# design.net
KiCad netlist of a schematic drawn in EAGLE
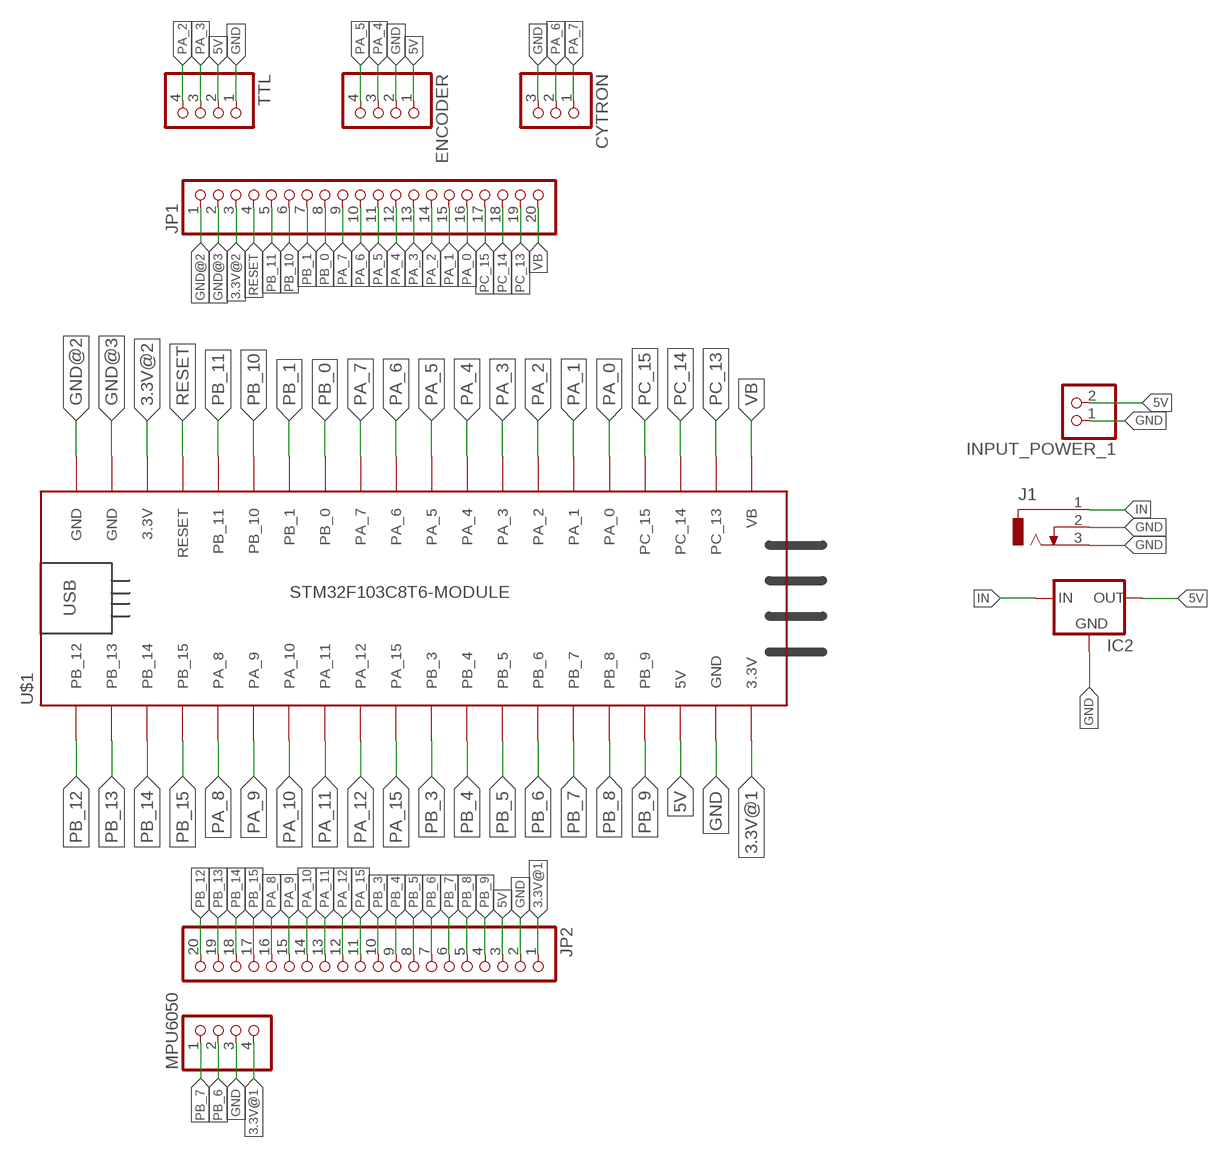
[diagram p0: schematic, sheet 1]

(export (version "E")
  (design (tool "Eeschema 10.0.6"))
  (components
    (comp (ref "CYTRON")
      (value "PINHD-1X3")
      (footprint "eagle-import:1X03")
      (libsource (lib "eagle-import") (part "PINHD-1X3"))
    )
    (comp (ref "ENCODER")
      (value "PINHD-1X4")
      (footprint "eagle-import:1X04")
      (libsource (lib "eagle-import") (part "PINHD-1X4"))
    )
    (comp (ref "IC2")
      (value "78XXS")
      (footprint "eagle-import:78XXS")
      (libsource (lib "eagle-import") (part "78XXS"))
    )
    (comp (ref "INPUT_POWER_1")
      (value "PINHD-1X2")
      (footprint "eagle-import:1X02")
      (libsource (lib "eagle-import") (part "PINHD-1X2"))
    )
    (comp (ref "J1")
      (value "CON_JACK")
      (footprint "eagle-import:DCJ0303")
      (libsource (lib "eagle-import") (part "CON_JACK"))
    )
    (comp (ref "JP1")
      (value "PINHD-1X20")
      (footprint "eagle-import:1X20")
      (libsource (lib "eagle-import") (part "PINHD-1X20"))
    )
    (comp (ref "JP2")
      (value "PINHD-1X20")
      (footprint "eagle-import:1X20")
      (libsource (lib "eagle-import") (part "PINHD-1X20"))
    )
    (comp (ref "MPU6050")
      (value "PINHD-1X4")
      (footprint "eagle-import:1X04")
      (libsource (lib "eagle-import") (part "PINHD-1X4"))
    )
    (comp (ref "TTL")
      (value "PINHD-1X4")
      (footprint "eagle-import:1X04")
      (libsource (lib "eagle-import") (part "PINHD-1X4"))
    )
    (comp (ref "U$1")
      (value "STM32F103C8T6-MODULE")
      (footprint "eagle-import:STM32F103C8T6-MODULE")
      (libsource (lib "eagle-import") (part "STM32F103C8T6-MODULE"))
    )
  )
  (nets
    (net (code "1") (name "3.3V@1") (class "Default")
      (node (ref "JP2") (pin "1") (pinfunction "1_1") (pintype "passive"))
      (node (ref "MPU6050") (pin "4") (pinfunction "4_4") (pintype "passive"))
      (node (ref "U$1") (pin "3.3V_1") (pinfunction "3.3V_3.3V_1") (pintype "bidirectional"))
    )
    (net (code "2") (name "3.3V@2") (class "Default")
      (node (ref "JP1") (pin "3") (pinfunction "3_3") (pintype "passive"))
      (node (ref "U$1") (pin "3.3V_2") (pinfunction "3.3V_3.3V_2") (pintype "bidirectional"))
    )
    (net (code "3") (name "5V") (class "Default")
      (node (ref "ENCODER") (pin "1") (pinfunction "1_1") (pintype "passive"))
      (node (ref "IC2") (pin "OUT") (pinfunction "OUT_OUT") (pintype "passive"))
      (node (ref "INPUT_POWER_1") (pin "2") (pinfunction "2_2") (pintype "passive"))
      (node (ref "JP2") (pin "3") (pinfunction "3_3") (pintype "passive"))
      (node (ref "TTL") (pin "2") (pinfunction "2_2") (pintype "passive"))
      (node (ref "U$1") (pin "5V") (pinfunction "5V_5V") (pintype "bidirectional"))
    )
    (net (code "4") (name "GND") (class "Default")
      (node (ref "CYTRON") (pin "3") (pinfunction "3_3") (pintype "passive"))
      (node (ref "ENCODER") (pin "2") (pinfunction "2_2") (pintype "passive"))
      (node (ref "IC2") (pin "GND") (pinfunction "GND_GND") (pintype "input"))
      (node (ref "INPUT_POWER_1") (pin "1") (pinfunction "1_1") (pintype "passive"))
      (node (ref "J1") (pin "2") (pinfunction "2_2") (pintype "passive"))
      (node (ref "J1") (pin "3") (pinfunction "3_3") (pintype "passive"))
      (node (ref "JP2") (pin "2") (pinfunction "2_2") (pintype "passive"))
      (node (ref "MPU6050") (pin "3") (pinfunction "3_3") (pintype "passive"))
      (node (ref "TTL") (pin "1") (pinfunction "1_1") (pintype "passive"))
      (node (ref "U$1") (pin "GND_1") (pinfunction "GND_GND_1") (pintype "bidirectional"))
    )
    (net (code "5") (name "GND@2") (class "Default")
      (node (ref "JP1") (pin "1") (pinfunction "1_1") (pintype "passive"))
      (node (ref "U$1") (pin "GND_3") (pinfunction "GND_GND_3") (pintype "power_in"))
    )
    (net (code "6") (name "GND@3") (class "Default")
      (node (ref "JP1") (pin "2") (pinfunction "2_2") (pintype "passive"))
      (node (ref "U$1") (pin "GND_2") (pinfunction "GND_GND_2") (pintype "bidirectional"))
    )
    (net (code "7") (name "IN") (class "Default")
      (node (ref "IC2") (pin "IN") (pinfunction "IN_IN") (pintype "input"))
      (node (ref "J1") (pin "1") (pinfunction "1_1") (pintype "passive"))
    )
    (net (code "8") (name "PA_0") (class "Default")
      (node (ref "JP1") (pin "16") (pinfunction "16_16") (pintype "passive"))
      (node (ref "U$1") (pin "PA_0") (pinfunction "PA_0_PA_0") (pintype "bidirectional"))
    )
    (net (code "9") (name "PA_1") (class "Default")
      (node (ref "JP1") (pin "15") (pinfunction "15_15") (pintype "passive"))
      (node (ref "U$1") (pin "PA_1") (pinfunction "PA_1_PA_1") (pintype "bidirectional"))
    )
    (net (code "10") (name "PA_2") (class "Default")
      (node (ref "JP1") (pin "14") (pinfunction "14_14") (pintype "passive"))
      (node (ref "TTL") (pin "4") (pinfunction "4_4") (pintype "passive"))
      (node (ref "U$1") (pin "PA_2") (pinfunction "PA_2_PA_2") (pintype "bidirectional"))
    )
    (net (code "11") (name "PA_3") (class "Default")
      (node (ref "JP1") (pin "13") (pinfunction "13_13") (pintype "passive"))
      (node (ref "TTL") (pin "3") (pinfunction "3_3") (pintype "passive"))
      (node (ref "U$1") (pin "PA_3") (pinfunction "PA_3_PA_3") (pintype "bidirectional"))
    )
    (net (code "12") (name "PA_4") (class "Default")
      (node (ref "ENCODER") (pin "3") (pinfunction "3_3") (pintype "passive"))
      (node (ref "JP1") (pin "12") (pinfunction "12_12") (pintype "passive"))
      (node (ref "U$1") (pin "PA_4") (pinfunction "PA_4_PA_4") (pintype "bidirectional"))
    )
    (net (code "13") (name "PA_5") (class "Default")
      (node (ref "ENCODER") (pin "4") (pinfunction "4_4") (pintype "passive"))
      (node (ref "JP1") (pin "11") (pinfunction "11_11") (pintype "passive"))
      (node (ref "U$1") (pin "PA_5") (pinfunction "PA_5_PA_5") (pintype "bidirectional"))
    )
    (net (code "14") (name "PA_6") (class "Default")
      (node (ref "CYTRON") (pin "2") (pinfunction "2_2") (pintype "passive"))
      (node (ref "JP1") (pin "10") (pinfunction "10_10") (pintype "passive"))
      (node (ref "U$1") (pin "PA_6") (pinfunction "PA_6_PA_6") (pintype "bidirectional"))
    )
    (net (code "15") (name "PA_7") (class "Default")
      (node (ref "CYTRON") (pin "1") (pinfunction "1_1") (pintype "passive"))
      (node (ref "JP1") (pin "9") (pinfunction "9_9") (pintype "passive"))
      (node (ref "U$1") (pin "PA_7") (pinfunction "PA_7_PA_7") (pintype "bidirectional"))
    )
    (net (code "16") (name "PA_8") (class "Default")
      (node (ref "JP2") (pin "16") (pinfunction "16_16") (pintype "passive"))
      (node (ref "U$1") (pin "PA_8") (pinfunction "PA_8_PA_8") (pintype "bidirectional"))
    )
    (net (code "17") (name "PA_9") (class "Default")
      (node (ref "JP2") (pin "15") (pinfunction "15_15") (pintype "passive"))
      (node (ref "U$1") (pin "PA_9") (pinfunction "PA_9_PA_9") (pintype "bidirectional"))
    )
    (net (code "18") (name "PA_10") (class "Default")
      (node (ref "JP2") (pin "14") (pinfunction "14_14") (pintype "passive"))
      (node (ref "U$1") (pin "PA_10") (pinfunction "PA_10_PA_10") (pintype "bidirectional"))
    )
    (net (code "19") (name "PA_11") (class "Default")
      (node (ref "JP2") (pin "13") (pinfunction "13_13") (pintype "passive"))
      (node (ref "U$1") (pin "PA_11") (pinfunction "PA_11_PA_11") (pintype "bidirectional"))
    )
    (net (code "20") (name "PA_12") (class "Default")
      (node (ref "JP2") (pin "12") (pinfunction "12_12") (pintype "passive"))
      (node (ref "U$1") (pin "PA_12") (pinfunction "PA_12_PA_12") (pintype "bidirectional"))
    )
    (net (code "21") (name "PA_15") (class "Default")
      (node (ref "JP2") (pin "11") (pinfunction "11_11") (pintype "passive"))
      (node (ref "U$1") (pin "PA_15") (pinfunction "PA_15_PA_15") (pintype "bidirectional"))
    )
    (net (code "22") (name "PB_0") (class "Default")
      (node (ref "JP1") (pin "8") (pinfunction "8_8") (pintype "passive"))
      (node (ref "U$1") (pin "PB_0") (pinfunction "PB_0_PB_0") (pintype "bidirectional"))
    )
    (net (code "23") (name "PB_1") (class "Default")
      (node (ref "JP1") (pin "7") (pinfunction "7_7") (pintype "passive"))
      (node (ref "U$1") (pin "PB_1") (pinfunction "PB_1_PB_1") (pintype "bidirectional"))
    )
    (net (code "24") (name "PB_3") (class "Default")
      (node (ref "JP2") (pin "10") (pinfunction "10_10") (pintype "passive"))
      (node (ref "U$1") (pin "PB_3") (pinfunction "PB_3_PB_3") (pintype "bidirectional"))
    )
    (net (code "25") (name "PB_4") (class "Default")
      (node (ref "JP2") (pin "9") (pinfunction "9_9") (pintype "passive"))
      (node (ref "U$1") (pin "PB_4") (pinfunction "PB_4_PB_4") (pintype "bidirectional"))
    )
    (net (code "26") (name "PB_5") (class "Default")
      (node (ref "JP2") (pin "8") (pinfunction "8_8") (pintype "passive"))
      (node (ref "U$1") (pin "PB_5") (pinfunction "PB_5_PB_5") (pintype "bidirectional"))
    )
    (net (code "27") (name "PB_6") (class "Default")
      (node (ref "JP2") (pin "7") (pinfunction "7_7") (pintype "passive"))
      (node (ref "MPU6050") (pin "2") (pinfunction "2_2") (pintype "passive"))
      (node (ref "U$1") (pin "PB_6") (pinfunction "PB_6_PB_6") (pintype "bidirectional"))
    )
    (net (code "28") (name "PB_7") (class "Default")
      (node (ref "JP2") (pin "6") (pinfunction "6_6") (pintype "passive"))
      (node (ref "MPU6050") (pin "1") (pinfunction "1_1") (pintype "passive"))
      (node (ref "U$1") (pin "PB_7") (pinfunction "PB_7_PB_7") (pintype "bidirectional"))
    )
    (net (code "29") (name "PB_8") (class "Default")
      (node (ref "JP2") (pin "5") (pinfunction "5_5") (pintype "passive"))
      (node (ref "U$1") (pin "PB_8") (pinfunction "PB_8_PB_8") (pintype "bidirectional"))
    )
    (net (code "30") (name "PB_9") (class "Default")
      (node (ref "JP2") (pin "4") (pinfunction "4_4") (pintype "passive"))
      (node (ref "U$1") (pin "PB_9") (pinfunction "PB_9_PB_9") (pintype "bidirectional"))
    )
    (net (code "31") (name "PB_10") (class "Default")
      (node (ref "JP1") (pin "6") (pinfunction "6_6") (pintype "passive"))
      (node (ref "U$1") (pin "PB_10") (pinfunction "PB_10_PB_10") (pintype "bidirectional"))
    )
    (net (code "32") (name "PB_11") (class "Default")
      (node (ref "JP1") (pin "5") (pinfunction "5_5") (pintype "passive"))
      (node (ref "U$1") (pin "PB_11") (pinfunction "PB_11_PB_11") (pintype "bidirectional"))
    )
    (net (code "33") (name "PB_12") (class "Default")
      (node (ref "JP2") (pin "20") (pinfunction "20_20") (pintype "passive"))
      (node (ref "U$1") (pin "PB_12") (pinfunction "PB_12_PB_12") (pintype "bidirectional"))
    )
    (net (code "34") (name "PB_13") (class "Default")
      (node (ref "JP2") (pin "19") (pinfunction "19_19") (pintype "passive"))
      (node (ref "U$1") (pin "PB_13") (pinfunction "PB_13_PB_13") (pintype "bidirectional"))
    )
    (net (code "35") (name "PB_14") (class "Default")
      (node (ref "JP2") (pin "18") (pinfunction "18_18") (pintype "passive"))
      (node (ref "U$1") (pin "PB_14") (pinfunction "PB_14_PB_14") (pintype "bidirectional"))
    )
    (net (code "36") (name "PB_15") (class "Default")
      (node (ref "JP2") (pin "17") (pinfunction "17_17") (pintype "passive"))
      (node (ref "U$1") (pin "PB_15") (pinfunction "PB_15_PB_15") (pintype "bidirectional"))
    )
    (net (code "37") (name "PC_13") (class "Default")
      (node (ref "JP1") (pin "19") (pinfunction "19_19") (pintype "passive"))
      (node (ref "U$1") (pin "PC_13") (pinfunction "PC_13_PC_13") (pintype "bidirectional"))
    )
    (net (code "38") (name "PC_14") (class "Default")
      (node (ref "JP1") (pin "18") (pinfunction "18_18") (pintype "passive"))
      (node (ref "U$1") (pin "PC_14") (pinfunction "PC_14_PC_14") (pintype "bidirectional"))
    )
    (net (code "39") (name "PC_15") (class "Default")
      (node (ref "JP1") (pin "17") (pinfunction "17_17") (pintype "passive"))
      (node (ref "U$1") (pin "PC_15") (pinfunction "PC_15_PC_15") (pintype "bidirectional"))
    )
    (net (code "40") (name "RESET") (class "Default")
      (node (ref "JP1") (pin "4") (pinfunction "4_4") (pintype "passive"))
      (node (ref "U$1") (pin "RESET") (pinfunction "RESET_RESET") (pintype "bidirectional"))
    )
    (net (code "41") (name "VB") (class "Default")
      (node (ref "JP1") (pin "20") (pinfunction "20_20") (pintype "passive"))
      (node (ref "U$1") (pin "VB") (pinfunction "VB_VB") (pintype "bidirectional"))
    )
  )
)
